# miniuno.net
KiCad netlist of a schematic drawn in EAGLE
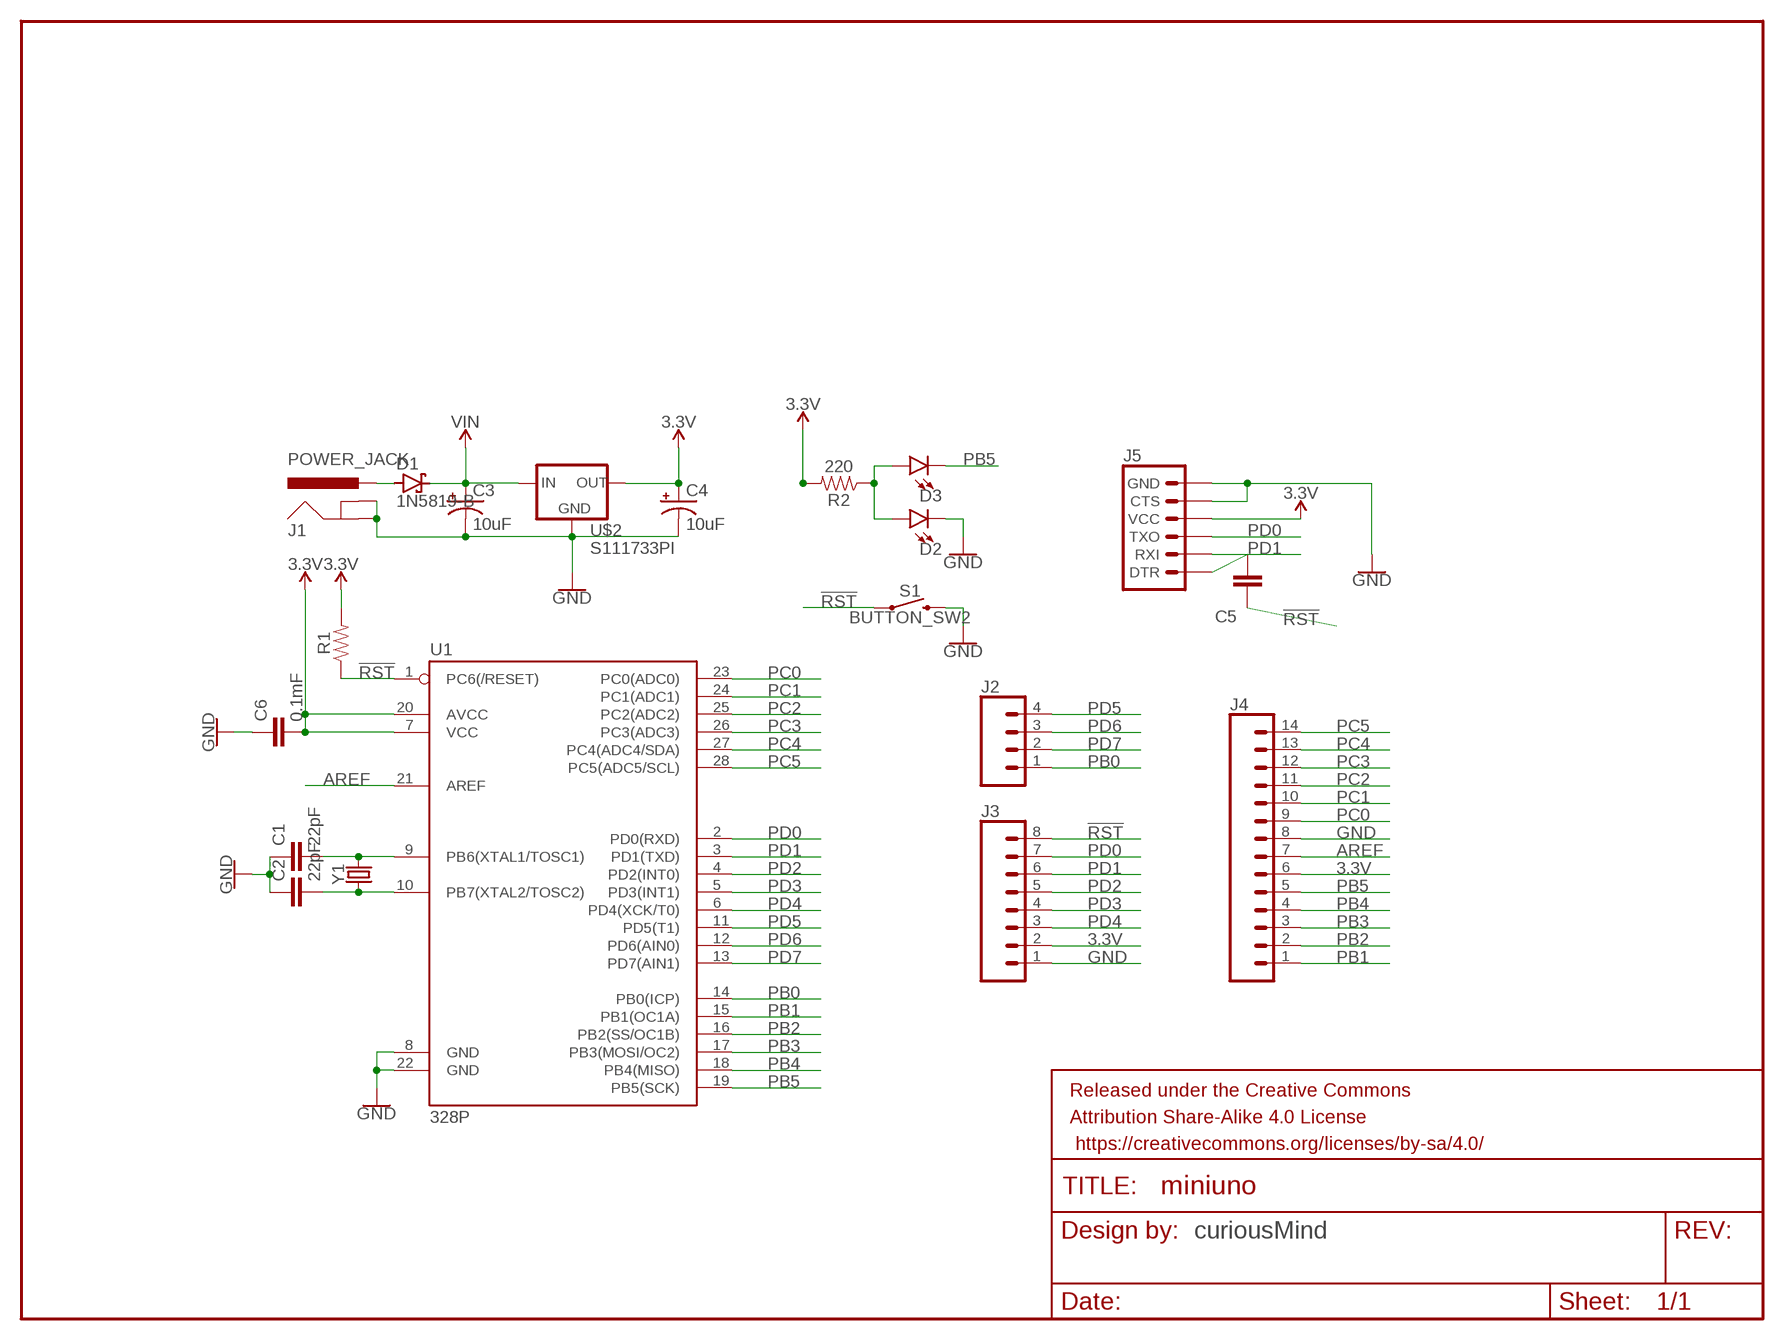
[diagram p0: schematic, sheet 1]

(export (version "E")
  (design (tool "Eeschema 10.0.6"))
  (components
    (comp (ref "C1")
      (value "22pF")
      (footprint "eagle-import:CAP-PTH-2.54")
      (libsource (lib "eagle-import") (part "22PF-PTH-2.54MM-200V-5%"))
    )
    (comp (ref "C2")
      (value "22pF")
      (footprint "eagle-import:CAP-PTH-2.54")
      (libsource (lib "eagle-import") (part "22PF-PTH-2.54MM-200V-5%"))
    )
    (comp (ref "C3")
      (value "10uF")
      (footprint "eagle-import:CPOL-RADIAL-2.5MM-5MM-KIT")
      (libsource (lib "eagle-import") (part "10UF-POLAR-RADIAL-2.5MM-KIT-25V-20%"))
    )
    (comp (ref "C4")
      (value "10uF")
      (footprint "eagle-import:CPOL-RADIAL-2.5MM-5MM-KIT")
      (libsource (lib "eagle-import") (part "10UF-POLAR-RADIAL-2.5MM-KIT-25V-20%"))
    )
    (comp (ref "C5")
      (value "0.1uF")
      (footprint "eagle-import:C5B2.5")
      (libsource (lib "eagle-import") (part "C5/2.5"))
    )
    (comp (ref "C6")
      (value "0.1mF")
      (footprint "eagle-import:CAP-PTH-2.54")
      (libsource (lib "eagle-import") (part "22PF-PTH-2.54MM-200V-5%"))
    )
    (comp (ref "D1")
      (value "1N5819-B")
      (footprint "eagle-import:DO41-7.6")
      (libsource (lib "eagle-import") (part "1N5819-B"))
    )
    (comp (ref "D2")
      (value "LED-3MM-NO_SILK")
      (footprint "eagle-import:LED_3MM-NS")
      (libsource (lib "eagle-import") (part "LED-3MM-NO_SILK"))
    )
    (comp (ref "D3")
      (value "LED-3MM-NO_SILK")
      (footprint "eagle-import:LED_3MM-NS")
      (libsource (lib "eagle-import") (part "LED-3MM-NO_SILK"))
    )
    (comp (ref "FRAME1")
      (value "FRAME-LETTER")
      (footprint "eagle-import:CREATIVE_COMMONS")
      (libsource (lib "eagle-import") (part "FRAME-LETTER"))
    )
    (comp (ref "J1")
      (value "POWER_JACK")
      (footprint "eagle-import:POWER_JACK_PTH")
      (libsource (lib "eagle-import") (part "POWER_JACK"))
    )
    (comp (ref "J2")
      (value "CONN_04")
      (footprint "eagle-import:1X04")
      (libsource (lib "eagle-import") (part "CONN_04"))
    )
    (comp (ref "J3")
      (value "CONN_08\"")
      (footprint "eagle-import:1X08")
      (libsource (lib "eagle-import") (part "CONN_08{dblquote}"))
    )
    (comp (ref "J4")
      (value "CONN_14")
      (footprint "eagle-import:1X14")
      (libsource (lib "eagle-import") (part "CONN_14"))
    )
    (comp (ref "J5")
      (value "6_PIN_SERIAL_TARGETPTH-KIT")
      (footprint "eagle-import:1X06-KIT")
      (libsource (lib "eagle-import") (part "6_PIN_SERIAL_TARGETPTH-KIT"))
    )
    (comp (ref "R1")
      (value "RESISTORAXIAL-0.3")
      (footprint "eagle-import:AXIAL-0.3")
      (libsource (lib "eagle-import") (part "RESISTORAXIAL-0.3"))
    )
    (comp (ref "R2")
      (value "220")
      (footprint "eagle-import:AXIAL-0.3")
      (libsource (lib "eagle-import") (part "RESISTORAXIAL-0.3"))
    )
    (comp (ref "S1")
      (value "BUTTON_SW2")
      (footprint "eagle-import:BUTTON_SW2")
      (libsource (lib "eagle-import") (part "BUTTON_SW2"))
    )
    (comp (ref "U$2")
      (value "S111733PI")
      (footprint "eagle-import:S1117XXPI-TO-220")
      (libsource (lib "eagle-import") (part "S111733PI"))
    )
    (comp (ref "U1")
      (value "328P")
      (footprint "eagle-import:DIP28")
      (libsource (lib "eagle-import") (part "ATMEGA328P_PDIP"))
    )
    (comp (ref "Y1")
      (value "CRYSTALPTH-HC49US")
      (footprint "eagle-import:HC49US")
      (libsource (lib "eagle-import") (part "CRYSTALPTH-HC49US"))
    )
  )
  (nets
    (net (code "1") (name "/AREF") (class "Default")
      (node (ref "J4") (pin "7") (pinfunction "7_7") (pintype "passive"))
      (node (ref "U1") (pin "21") (pinfunction "AREF_21") (pintype "bidirectional"))
    )
    (net (code "2") (name "/PB0") (class "Default")
      (node (ref "J2") (pin "1") (pinfunction "1_1") (pintype "passive"))
      (node (ref "U1") (pin "14") (pinfunction "PB0(ICP)_14") (pintype "bidirectional"))
    )
    (net (code "3") (name "/PB1") (class "Default")
      (node (ref "J4") (pin "1") (pinfunction "1_1") (pintype "passive"))
      (node (ref "U1") (pin "15") (pinfunction "PB1(OC1A)_15") (pintype "bidirectional"))
    )
    (net (code "4") (name "/PB2") (class "Default")
      (node (ref "J4") (pin "2") (pinfunction "2_2") (pintype "passive"))
      (node (ref "U1") (pin "16") (pinfunction "PB2(SS/OC1B)_16") (pintype "bidirectional"))
    )
    (net (code "5") (name "/PB3") (class "Default")
      (node (ref "J4") (pin "3") (pinfunction "3_3") (pintype "passive"))
      (node (ref "U1") (pin "17") (pinfunction "PB3(MOSI/OC2)_17") (pintype "bidirectional"))
    )
    (net (code "6") (name "/PB4") (class "Default")
      (node (ref "J4") (pin "4") (pinfunction "4_4") (pintype "passive"))
      (node (ref "U1") (pin "18") (pinfunction "PB4(MISO)_18") (pintype "bidirectional"))
    )
    (net (code "7") (name "/PB5") (class "Default")
      (node (ref "D3") (pin "K") (pinfunction "C_K") (pintype "passive"))
      (node (ref "J4") (pin "5") (pinfunction "5_5") (pintype "passive"))
      (node (ref "U1") (pin "19") (pinfunction "PB5(SCK)_19") (pintype "bidirectional"))
    )
    (net (code "8") (name "/PC0") (class "Default")
      (node (ref "J4") (pin "9") (pinfunction "9_9") (pintype "passive"))
      (node (ref "U1") (pin "23") (pinfunction "PC0(ADC0)_23") (pintype "bidirectional"))
    )
    (net (code "9") (name "/PC1") (class "Default")
      (node (ref "J4") (pin "10") (pinfunction "10_10") (pintype "passive"))
      (node (ref "U1") (pin "24") (pinfunction "PC1(ADC1)_24") (pintype "bidirectional"))
    )
    (net (code "10") (name "/PC2") (class "Default")
      (node (ref "J4") (pin "11") (pinfunction "11_11") (pintype "passive"))
      (node (ref "U1") (pin "25") (pinfunction "PC2(ADC2)_25") (pintype "bidirectional"))
    )
    (net (code "11") (name "/PC3") (class "Default")
      (node (ref "J4") (pin "12") (pinfunction "12_12") (pintype "passive"))
      (node (ref "U1") (pin "26") (pinfunction "PC3(ADC3)_26") (pintype "bidirectional"))
    )
    (net (code "12") (name "/PC4") (class "Default")
      (node (ref "J4") (pin "13") (pinfunction "13_13") (pintype "passive"))
      (node (ref "U1") (pin "27") (pinfunction "PC4(ADC4/SDA)_27") (pintype "bidirectional"))
    )
    (net (code "13") (name "/PC5") (class "Default")
      (node (ref "J4") (pin "14") (pinfunction "14_14") (pintype "passive"))
      (node (ref "U1") (pin "28") (pinfunction "PC5(ADC5/SCL)_28") (pintype "bidirectional"))
    )
    (net (code "14") (name "/PD0") (class "Default")
      (node (ref "J3") (pin "7") (pinfunction "7_7") (pintype "passive"))
      (node (ref "J5") (pin "3") (pinfunction "TXO_3") (pintype "passive"))
      (node (ref "U1") (pin "2") (pinfunction "PD0(RXD)_2") (pintype "bidirectional"))
    )
    (net (code "15") (name "/PD1") (class "Default")
      (node (ref "J3") (pin "6") (pinfunction "6_6") (pintype "passive"))
      (node (ref "J5") (pin "2") (pinfunction "RXI_2") (pintype "passive"))
      (node (ref "U1") (pin "3") (pinfunction "PD1(TXD)_3") (pintype "bidirectional"))
    )
    (net (code "16") (name "/PD2") (class "Default")
      (node (ref "J3") (pin "5") (pinfunction "5_5") (pintype "passive"))
      (node (ref "U1") (pin "4") (pinfunction "PD2(INT0)_4") (pintype "bidirectional"))
    )
    (net (code "17") (name "/PD3") (class "Default")
      (node (ref "J3") (pin "4") (pinfunction "4_4") (pintype "passive"))
      (node (ref "U1") (pin "5") (pinfunction "PD3(INT1)_5") (pintype "bidirectional"))
    )
    (net (code "18") (name "/PD4") (class "Default")
      (node (ref "J3") (pin "3") (pinfunction "3_3") (pintype "passive"))
      (node (ref "U1") (pin "6") (pinfunction "PD4(XCK/T0)_6") (pintype "bidirectional"))
    )
    (net (code "19") (name "/PD5") (class "Default")
      (node (ref "J2") (pin "4") (pinfunction "4_4") (pintype "passive"))
      (node (ref "U1") (pin "11") (pinfunction "PD5(T1)_11") (pintype "bidirectional"))
    )
    (net (code "20") (name "/PD6") (class "Default")
      (node (ref "J2") (pin "3") (pinfunction "3_3") (pintype "passive"))
      (node (ref "U1") (pin "12") (pinfunction "PD6(AIN0)_12") (pintype "bidirectional"))
    )
    (net (code "21") (name "/PD7") (class "Default")
      (node (ref "J2") (pin "2") (pinfunction "2_2") (pintype "passive"))
      (node (ref "U1") (pin "13") (pinfunction "PD7(AIN1)_13") (pintype "bidirectional"))
    )
    (net (code "22") (name "/~{RST}") (class "Default")
      (node (ref "C5") (pin "1") (pinfunction "1_1") (pintype "passive"))
      (node (ref "J3") (pin "8") (pinfunction "8_8") (pintype "passive"))
      (node (ref "R1") (pin "P$1") (pinfunction "1_P$1") (pintype "passive"))
      (node (ref "S1") (pin "1") (pinfunction "1_1") (pintype "passive"))
      (node (ref "U1") (pin "1") (pinfunction "PC6(/RESET)_1") (pintype "bidirectional"))
    )
    (net (code "23") (name "3.3V") (class "Default")
      (node (ref "C4") (pin "1") (pinfunction "+_1") (pintype "passive"))
      (node (ref "C6") (pin "2") (pinfunction "2_2") (pintype "passive"))
      (node (ref "J3") (pin "2") (pinfunction "2_2") (pintype "passive"))
      (node (ref "J4") (pin "6") (pinfunction "6_6") (pintype "passive"))
      (node (ref "J5") (pin "4") (pinfunction "VCC_4") (pintype "passive"))
      (node (ref "R1") (pin "P$2") (pinfunction "2_P$2") (pintype "passive"))
      (node (ref "R2") (pin "P$2") (pinfunction "2_P$2") (pintype "passive"))
      (node (ref "U$2") (pin "OUT") (pinfunction "OUT_OUT") (pintype "passive"))
      (node (ref "U1") (pin "20") (pinfunction "AVCC_20") (pintype "bidirectional"))
      (node (ref "U1") (pin "7") (pinfunction "VCC_7") (pintype "bidirectional"))
    )
    (net (code "24") (name "GND") (class "Default")
      (node (ref "C1") (pin "1") (pinfunction "1_1") (pintype "passive"))
      (node (ref "C2") (pin "1") (pinfunction "1_1") (pintype "passive"))
      (node (ref "C3") (pin "2") (pinfunction "-_2") (pintype "passive"))
      (node (ref "C4") (pin "2") (pinfunction "-_2") (pintype "passive"))
      (node (ref "C6") (pin "1") (pinfunction "1_1") (pintype "passive"))
      (node (ref "D2") (pin "K") (pinfunction "C_K") (pintype "passive"))
      (node (ref "J1") (pin "GND") (pinfunction "GND_GND") (pintype "bidirectional"))
      (node (ref "J1") (pin "GNDBREAK") (pinfunction "GNDBREAK_GNDBREAK") (pintype "bidirectional"))
      (node (ref "J3") (pin "1") (pinfunction "1_1") (pintype "passive"))
      (node (ref "J4") (pin "8") (pinfunction "8_8") (pintype "passive"))
      (node (ref "J5") (pin "5") (pinfunction "CTS_5") (pintype "passive"))
      (node (ref "J5") (pin "6") (pinfunction "GND_6") (pintype "passive"))
      (node (ref "S1") (pin "2") (pinfunction "2_2") (pintype "passive"))
      (node (ref "U$2") (pin "GND") (pinfunction "GND_GND") (pintype "input"))
      (node (ref "U1") (pin "22") (pinfunction "GND_22") (pintype "bidirectional"))
      (node (ref "U1") (pin "8") (pinfunction "GND_8") (pintype "bidirectional"))
    )
    (net (code "25") (name "Net-(D1-PadA)") (class "Default")
      (node (ref "D1") (pin "A") (pinfunction "A_A") (pintype "passive"))
      (node (ref "J1") (pin "PWR") (pinfunction "PWR_PWR") (pintype "bidirectional"))
    )
    (net (code "26") (name "Net-(J5-DTR)") (class "Default")
      (node (ref "C5") (pin "2") (pinfunction "2_2") (pintype "passive"))
      (node (ref "J5") (pin "1") (pinfunction "DTR_1") (pintype "passive"))
    )
    (net (code "27") (name "Net-(R2-1)") (class "Default")
      (node (ref "D2") (pin "A") (pinfunction "A_A") (pintype "passive"))
      (node (ref "D3") (pin "A") (pinfunction "A_A") (pintype "passive"))
      (node (ref "R2") (pin "P$1") (pinfunction "1_P$1") (pintype "passive"))
    )
    (net (code "28") (name "Net-(U1-PB6(XTAL1{slash}TOSC1))") (class "Default")
      (node (ref "C1") (pin "2") (pinfunction "2_2") (pintype "passive"))
      (node (ref "U1") (pin "9") (pinfunction "PB6(XTAL1/TOSC1)_9") (pintype "bidirectional"))
      (node (ref "Y1") (pin "2") (pinfunction "2_2") (pintype "passive"))
    )
    (net (code "29") (name "Net-(U1-PB7(XTAL2{slash}TOSC2))") (class "Default")
      (node (ref "C2") (pin "2") (pinfunction "2_2") (pintype "passive"))
      (node (ref "U1") (pin "10") (pinfunction "PB7(XTAL2/TOSC2)_10") (pintype "bidirectional"))
      (node (ref "Y1") (pin "1") (pinfunction "1_1") (pintype "passive"))
    )
    (net (code "30") (name "VIN") (class "Default")
      (node (ref "C3") (pin "1") (pinfunction "+_1") (pintype "passive"))
      (node (ref "D1") (pin "C") (pinfunction "C_C") (pintype "passive"))
      (node (ref "U$2") (pin "IN") (pinfunction "IN_IN") (pintype "input"))
    )
  )
)
